# LED_Ring_Dimmer.net
KiCad netlist of a schematic drawn in EAGLE
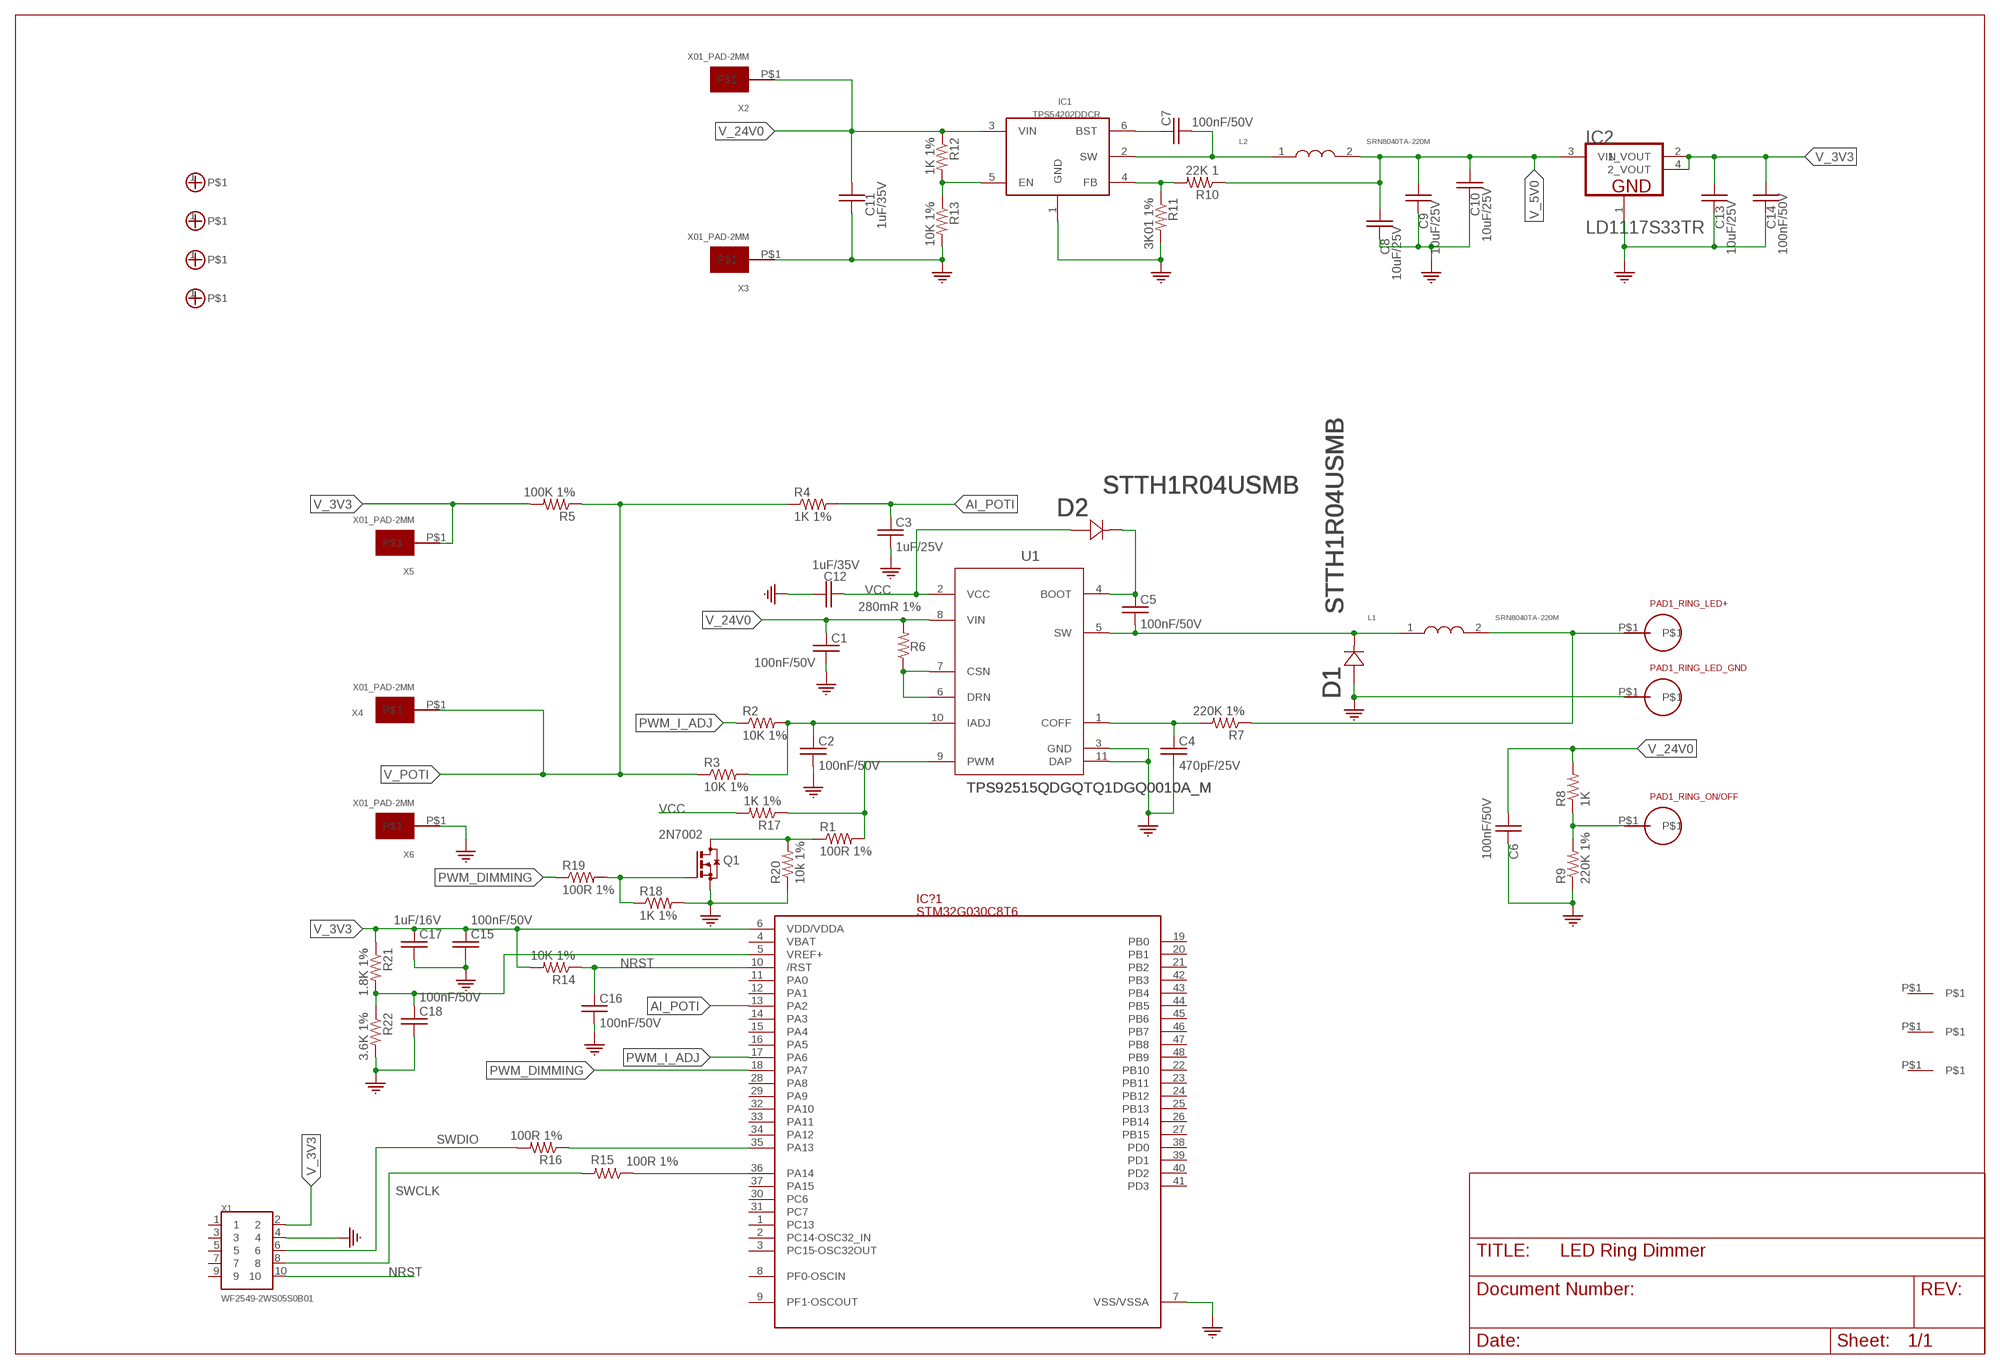
[diagram p0: schematic, sheet 1]

(export (version "E")
  (design (tool "Eeschema 10.0.6"))
  (components
    (comp (ref "C1")
      (value "100nF/50V")
      (footprint "eagle-import:EIA0603")
      (libsource (lib "eagle-import") (part "C_0603EIA0603"))
    )
    (comp (ref "C2")
      (value "100nF/50V")
      (footprint "eagle-import:EIA0603")
      (libsource (lib "eagle-import") (part "C_0603EIA0603"))
    )
    (comp (ref "C3")
      (value "1uF/25V")
      (footprint "eagle-import:EIA0603")
      (libsource (lib "eagle-import") (part "C_0603EIA0603"))
    )
    (comp (ref "C4")
      (value "470pF/25V")
      (footprint "eagle-import:EIA0603")
      (libsource (lib "eagle-import") (part "C_0603EIA0603"))
    )
    (comp (ref "C5")
      (value "100nF/50V")
      (footprint "eagle-import:EIA0603")
      (libsource (lib "eagle-import") (part "C_0603EIA0603"))
    )
    (comp (ref "C6")
      (value "100nF/50V")
      (footprint "eagle-import:EIA0603")
      (libsource (lib "eagle-import") (part "C_0603EIA0603"))
    )
    (comp (ref "C7")
      (value "100nF/50V")
      (footprint "eagle-import:EIA0603")
      (libsource (lib "eagle-import") (part "C_0603EIA0603"))
    )
    (comp (ref "C8")
      (value "10uF/25V")
      (footprint "eagle-import:EIA0603")
      (libsource (lib "eagle-import") (part "C_0603EIA0603"))
    )
    (comp (ref "C9")
      (value "10uF/25V")
      (footprint "eagle-import:EIA0603")
      (libsource (lib "eagle-import") (part "C_0603EIA0603"))
    )
    (comp (ref "C10")
      (value "10uF/25V")
      (footprint "eagle-import:EIA0603")
      (libsource (lib "eagle-import") (part "C_0603EIA0603"))
    )
    (comp (ref "C11")
      (value "1uF/35V")
      (footprint "eagle-import:EIA0603")
      (libsource (lib "eagle-import") (part "C_0603EIA0603"))
    )
    (comp (ref "C12")
      (value "1uF/35V")
      (footprint "eagle-import:EIA0603")
      (libsource (lib "eagle-import") (part "C_0603EIA0603"))
    )
    (comp (ref "C13")
      (value "10uF/25V")
      (footprint "eagle-import:EIA0603")
      (libsource (lib "eagle-import") (part "C_0603EIA0603"))
    )
    (comp (ref "C14")
      (value "100nF/50V")
      (footprint "eagle-import:EIA0603")
      (libsource (lib "eagle-import") (part "C_0603EIA0603"))
    )
    (comp (ref "C15")
      (value "100nF/50V")
      (footprint "eagle-import:EIA0603")
      (libsource (lib "eagle-import") (part "C_0603EIA0603"))
    )
    (comp (ref "C16")
      (value "100nF/50V")
      (footprint "eagle-import:EIA0603")
      (libsource (lib "eagle-import") (part "C_0603EIA0603"))
    )
    (comp (ref "C17")
      (value "1uF/16V")
      (footprint "eagle-import:EIA0603")
      (libsource (lib "eagle-import") (part "C_0603EIA0603"))
    )
    (comp (ref "C18")
      (value "100nF/50V")
      (footprint "eagle-import:EIA0603")
      (libsource (lib "eagle-import") (part "C_0603EIA0603"))
    )
    (comp (ref "D1")
      (value "STTH1R04USMB")
      (footprint "eagle-import:SMB")
      (libsource (lib "eagle-import") (part "STTH1R04USMB"))
    )
    (comp (ref "D2")
      (value "STTH1R04USMB")
      (footprint "eagle-import:SMB")
      (libsource (lib "eagle-import") (part "STTH1R04USMB"))
    )
    (comp (ref "FID1")
      (value "FIDUCIAL")
      (footprint "eagle-import:FIDUCIAL")
      (libsource (lib "eagle-import") (part "FIDUCIAL"))
    )
    (comp (ref "FID2")
      (value "FIDUCIAL")
      (footprint "eagle-import:FIDUCIAL")
      (libsource (lib "eagle-import") (part "FIDUCIAL"))
    )
    (comp (ref "FID3")
      (value "FIDUCIAL")
      (footprint "eagle-import:FIDUCIAL")
      (libsource (lib "eagle-import") (part "FIDUCIAL"))
    )
    (comp (ref "IC1")
      (value "TPS54202DDCR")
      (footprint "eagle-import:SOT23-6")
      (fields (field (name "MFR") "Texas Instruments"))
      (libsource (lib "eagle-import") (part "TPS54202DDCR"))
    )
    (comp (ref "IC2")
      (value "LD1117S33TR")
      (footprint "eagle-import:SOT223_LD1117S33TR")
      (fields (field (name "MFR") "STmicro, Diodes, TI,"))
      (libsource (lib "eagle-import") (part "LD1117S33TR"))
    )
    (comp (ref "IC?1")
      (value "STM32G030C8T6")
      (footprint "eagle-import:LQFP48")
      (libsource (lib "eagle-import") (part "STM32G030C8T6"))
    )
    (comp (ref "L1")
      (value "SRN8040TA-220M")
      (footprint "eagle-import:SRN8040TA-220M")
      (fields (field (name "MFR") "Bourns"))
      (libsource (lib "eagle-import") (part "SRN8040TA-220M"))
    )
    (comp (ref "L2")
      (value "SRN8040TA-220M")
      (footprint "eagle-import:SRN8040TA-220M")
      (fields (field (name "MFR") "Bourns"))
      (libsource (lib "eagle-import") (part "SRN8040TA-220M"))
    )
    (comp (ref "M1")
      (value "M_HOLE_3M")
      (footprint "eagle-import:PCB_SCREW_M3_POWER")
      (libsource (lib "eagle-import") (part "M_HOLE_3M"))
    )
    (comp (ref "M2")
      (value "M_HOLE_3M")
      (footprint "eagle-import:PCB_SCREW_M3_POWER")
      (libsource (lib "eagle-import") (part "M_HOLE_3M"))
    )
    (comp (ref "M3")
      (value "M_HOLE_3M")
      (footprint "eagle-import:PCB_SCREW_M3_POWER")
      (libsource (lib "eagle-import") (part "M_HOLE_3M"))
    )
    (comp (ref "M4")
      (value "M_HOLE_3M")
      (footprint "eagle-import:PCB_SCREW_M3_POWER")
      (libsource (lib "eagle-import") (part "M_HOLE_3M"))
    )
    (comp (ref "PAD1_RING_LED+")
      (value "THT_PAD_5MM")
      (footprint "eagle-import:THT_PAD_D5.0")
      (libsource (lib "eagle-import") (part "THT_PAD_5MM"))
    )
    (comp (ref "PAD1_RING_LED_GND")
      (value "THT_PAD_5MM")
      (footprint "eagle-import:THT_PAD_D5.0")
      (libsource (lib "eagle-import") (part "THT_PAD_5MM"))
    )
    (comp (ref "PAD1_RING_ON/OFF")
      (value "THT_PAD_5MM")
      (footprint "eagle-import:THT_PAD_D5.0")
      (libsource (lib "eagle-import") (part "THT_PAD_5MM"))
    )
    (comp (ref "Q1")
      (value "2N7002")
      (footprint "eagle-import:SOT23")
      (fields (field (name "MFR") "Diodes, Guangdong Hotetech,NXP"))
      (libsource (lib "eagle-import") (part "2N7002"))
    )
    (comp (ref "R1")
      (value "100R 1%")
      (footprint "eagle-import:EIA0603")
      (libsource (lib "eagle-import") (part "R_0603"))
    )
    (comp (ref "R2")
      (value "10K 1%")
      (footprint "eagle-import:EIA0603")
      (libsource (lib "eagle-import") (part "R_0603"))
    )
    (comp (ref "R3")
      (value "10K 1%")
      (footprint "eagle-import:EIA0603")
      (libsource (lib "eagle-import") (part "R_0603"))
    )
    (comp (ref "R4")
      (value "1K 1%")
      (footprint "eagle-import:EIA0603")
      (libsource (lib "eagle-import") (part "R_0603"))
    )
    (comp (ref "R5")
      (value "100K 1%")
      (footprint "eagle-import:EIA0603")
      (libsource (lib "eagle-import") (part "R_0603"))
    )
    (comp (ref "R6")
      (value "280mR 1%")
      (footprint "eagle-import:EIA1206")
      (libsource (lib "eagle-import") (part "R_1206EIA1206"))
    )
    (comp (ref "R7")
      (value "220K 1%")
      (footprint "eagle-import:EIA0603")
      (libsource (lib "eagle-import") (part "R_0603"))
    )
    (comp (ref "R8")
      (value "1K")
      (footprint "eagle-import:EIA0603")
      (libsource (lib "eagle-import") (part "R_0603"))
    )
    (comp (ref "R9")
      (value "220K 1%")
      (footprint "eagle-import:EIA0603")
      (libsource (lib "eagle-import") (part "R_0603"))
    )
    (comp (ref "R10")
      (value "22K 1")
      (footprint "eagle-import:EIA0603")
      (libsource (lib "eagle-import") (part "R_0603"))
    )
    (comp (ref "R11")
      (value "3K01 1%")
      (footprint "eagle-import:EIA0603")
      (libsource (lib "eagle-import") (part "R_0603"))
    )
    (comp (ref "R12")
      (value "1K 1%")
      (footprint "eagle-import:EIA0603")
      (libsource (lib "eagle-import") (part "R_0603"))
    )
    (comp (ref "R13")
      (value "10K 1%")
      (footprint "eagle-import:EIA0603")
      (libsource (lib "eagle-import") (part "R_0603"))
    )
    (comp (ref "R14")
      (value "10K 1%")
      (footprint "eagle-import:EIA0603")
      (libsource (lib "eagle-import") (part "R_0603"))
    )
    (comp (ref "R15")
      (value "100R 1%")
      (footprint "eagle-import:EIA0603")
      (libsource (lib "eagle-import") (part "R_0603"))
    )
    (comp (ref "R16")
      (value "100R 1%")
      (footprint "eagle-import:EIA0603")
      (libsource (lib "eagle-import") (part "R_0603"))
    )
    (comp (ref "R17")
      (value "1K 1%")
      (footprint "eagle-import:EIA0603")
      (libsource (lib "eagle-import") (part "R_0603"))
    )
    (comp (ref "R18")
      (value "1K 1%")
      (footprint "eagle-import:EIA0603")
      (libsource (lib "eagle-import") (part "R_0603"))
    )
    (comp (ref "R19")
      (value "100R 1%")
      (footprint "eagle-import:EIA0603")
      (libsource (lib "eagle-import") (part "R_0603"))
    )
    (comp (ref "R20")
      (value "10k 1%")
      (footprint "eagle-import:EIA0603")
      (libsource (lib "eagle-import") (part "R_0603"))
    )
    (comp (ref "R21")
      (value "1.8K 1%")
      (footprint "eagle-import:EIA0603")
      (libsource (lib "eagle-import") (part "R_0603"))
    )
    (comp (ref "R22")
      (value "3.6K 1%")
      (footprint "eagle-import:EIA0603")
      (libsource (lib "eagle-import") (part "R_0603"))
    )
    (comp (ref "U1")
      (value "TPS92515QDGQTQ1DGQ0010A_M")
      (footprint "eagle-import:DGQ0010A_M")
      (fields
        (field (name "MFR") "Texas Instruments")
        (field (name "COPYRIGHT") "Copyright (C) 2023 Ultra Librarian. All rights reserved.")
      )
      (libsource (lib "eagle-import") (part "TPS92515QDGQTQ1DGQ0010A_M"))
    )
    (comp (ref "X1")
      (value "WF2549-2WS05S0B01")
      (footprint "eagle-import:X10_100MIL_2XROW_VERT")
      (fields (field (name "MFR") "WCON"))
      (libsource (lib "eagle-import") (part "WF2549-2WS05S0B01"))
    )
    (comp (ref "X2")
      (value "X01_PAD-2MM")
      (footprint "eagle-import:X01_PAD-2MM")
      (libsource (lib "eagle-import") (part "X01_PAD-2MM"))
    )
    (comp (ref "X3")
      (value "X01_PAD-2MM")
      (footprint "eagle-import:X01_PAD-2MM")
      (libsource (lib "eagle-import") (part "X01_PAD-2MM"))
    )
    (comp (ref "X4")
      (value "X01_PAD-2MM")
      (footprint "eagle-import:X01_PAD-2MM")
      (libsource (lib "eagle-import") (part "X01_PAD-2MM"))
    )
    (comp (ref "X5")
      (value "X01_PAD-2MM")
      (footprint "eagle-import:X01_PAD-2MM")
      (libsource (lib "eagle-import") (part "X01_PAD-2MM"))
    )
    (comp (ref "X6")
      (value "X01_PAD-2MM")
      (footprint "eagle-import:X01_PAD-2MM")
      (libsource (lib "eagle-import") (part "X01_PAD-2MM"))
    )
  )
  (nets
    (net (code "1") (name "/NRST") (class "Default")
      (node (ref "C16") (pin "1") (pinfunction "1_1") (pintype "passive"))
      (node (ref "IC?1") (pin "10") (pinfunction "/RST_10") (pintype "bidirectional"))
      (node (ref "R14") (pin "1") (pinfunction "1_1") (pintype "passive"))
      (node (ref "X1") (pin "10") (pinfunction "10_10") (pintype "bidirectional"))
    )
    (net (code "2") (name "/SWCLK") (class "Default")
      (node (ref "R15") (pin "2") (pinfunction "2_2") (pintype "passive"))
      (node (ref "X1") (pin "8") (pinfunction "8_8") (pintype "bidirectional"))
    )
    (net (code "3") (name "/SWDIO") (class "Default")
      (node (ref "R16") (pin "2") (pinfunction "2_2") (pintype "passive"))
      (node (ref "X1") (pin "6") (pinfunction "6_6") (pintype "bidirectional"))
    )
    (net (code "4") (name "/VCC") (class "Default")
      (node (ref "C12") (pin "2") (pinfunction "2_2") (pintype "passive"))
      (node (ref "D2") (pin "A") (pinfunction "A_A") (pintype "passive"))
      (node (ref "R17") (pin "2") (pinfunction "2_2") (pintype "passive"))
      (node (ref "U1") (pin "2") (pinfunction "VCC_2") (pintype "power_in"))
    )
    (net (code "5") (name "AI_POTI") (class "Default")
      (node (ref "C3") (pin "1") (pinfunction "1_1") (pintype "passive"))
      (node (ref "IC?1") (pin "13") (pinfunction "PA2_13") (pintype "bidirectional"))
      (node (ref "R4") (pin "2") (pinfunction "2_2") (pintype "passive"))
    )
    (net (code "6") (name "GND") (class "Default")
      (node (ref "C1") (pin "2") (pinfunction "2_2") (pintype "passive"))
      (node (ref "C10") (pin "2") (pinfunction "2_2") (pintype "passive"))
      (node (ref "C11") (pin "2") (pinfunction "2_2") (pintype "passive"))
      (node (ref "C12") (pin "1") (pinfunction "1_1") (pintype "passive"))
      (node (ref "C13") (pin "2") (pinfunction "2_2") (pintype "passive"))
      (node (ref "C14") (pin "2") (pinfunction "2_2") (pintype "passive"))
      (node (ref "C15") (pin "2") (pinfunction "2_2") (pintype "passive"))
      (node (ref "C16") (pin "2") (pinfunction "2_2") (pintype "passive"))
      (node (ref "C17") (pin "2") (pinfunction "2_2") (pintype "passive"))
      (node (ref "C18") (pin "2") (pinfunction "2_2") (pintype "passive"))
      (node (ref "C2") (pin "2") (pinfunction "2_2") (pintype "passive"))
      (node (ref "C3") (pin "2") (pinfunction "2_2") (pintype "passive"))
      (node (ref "C4") (pin "2") (pinfunction "2_2") (pintype "passive"))
      (node (ref "C6") (pin "2") (pinfunction "2_2") (pintype "passive"))
      (node (ref "C8") (pin "2") (pinfunction "2_2") (pintype "passive"))
      (node (ref "C9") (pin "2") (pinfunction "2_2") (pintype "passive"))
      (node (ref "D1") (pin "A") (pinfunction "A_A") (pintype "passive"))
      (node (ref "IC1") (pin "1") (pinfunction "GND_1") (pintype "bidirectional"))
      (node (ref "IC2") (pin "1") (pinfunction "GND_1") (pintype "power_in"))
      (node (ref "IC?1") (pin "7") (pinfunction "VSS/VSSA_7") (pintype "bidirectional"))
      (node (ref "PAD1_RING_LED_GND") (pin "P$1") (pinfunction "P$1_P$1") (pintype "bidirectional"))
      (node (ref "Q1") (pin "2") (pinfunction "S_2") (pintype "passive"))
      (node (ref "R11") (pin "2") (pinfunction "2_2") (pintype "passive"))
      (node (ref "R13") (pin "2") (pinfunction "2_2") (pintype "passive"))
      (node (ref "R18") (pin "2") (pinfunction "2_2") (pintype "passive"))
      (node (ref "R20") (pin "1") (pinfunction "1_1") (pintype "passive"))
      (node (ref "R22") (pin "2") (pinfunction "2_2") (pintype "passive"))
      (node (ref "R9") (pin "1") (pinfunction "1_1") (pintype "passive"))
      (node (ref "U1") (pin "11") (pinfunction "DAP_11") (pintype "power_in"))
      (node (ref "U1") (pin "3") (pinfunction "GND_3") (pintype "power_in"))
      (node (ref "X1") (pin "4") (pinfunction "4_4") (pintype "bidirectional"))
      (node (ref "X3") (pin "P$1") (pinfunction "P$1_P$1") (pintype "bidirectional"))
      (node (ref "X6") (pin "P$1") (pinfunction "P$1_P$1") (pintype "bidirectional"))
    )
    (net (code "7") (name "Net-(D1-C)") (class "Default")
      (node (ref "C5") (pin "2") (pinfunction "2_2") (pintype "passive"))
      (node (ref "D1") (pin "K") (pinfunction "C_K") (pintype "passive"))
      (node (ref "L1") (pin "1") (pinfunction "P$1_1") (pintype "bidirectional"))
      (node (ref "U1") (pin "5") (pinfunction "SW_5") (pintype "power_in"))
    )
    (net (code "8") (name "Net-(D2-C)") (class "Default")
      (node (ref "C5") (pin "1") (pinfunction "1_1") (pintype "passive"))
      (node (ref "D2") (pin "K") (pinfunction "C_K") (pintype "passive"))
      (node (ref "U1") (pin "4") (pinfunction "BOOT_4") (pintype "power_in"))
    )
    (net (code "9") (name "Net-(IC1-BST)") (class "Default")
      (node (ref "C7") (pin "1") (pinfunction "1_1") (pintype "passive"))
      (node (ref "IC1") (pin "6") (pinfunction "BST_6") (pintype "bidirectional"))
    )
    (net (code "10") (name "Net-(IC1-EN)") (class "Default")
      (node (ref "IC1") (pin "5") (pinfunction "EN_5") (pintype "bidirectional"))
      (node (ref "R12") (pin "2") (pinfunction "2_2") (pintype "passive"))
      (node (ref "R13") (pin "1") (pinfunction "1_1") (pintype "passive"))
    )
    (net (code "11") (name "Net-(IC1-FB)") (class "Default")
      (node (ref "IC1") (pin "4") (pinfunction "FB_4") (pintype "bidirectional"))
      (node (ref "R10") (pin "2") (pinfunction "2_2") (pintype "passive"))
      (node (ref "R11") (pin "1") (pinfunction "1_1") (pintype "passive"))
    )
    (net (code "12") (name "Net-(IC1-SW)") (class "Default")
      (node (ref "C7") (pin "2") (pinfunction "2_2") (pintype "passive"))
      (node (ref "IC1") (pin "2") (pinfunction "SW_2") (pintype "bidirectional"))
      (node (ref "L2") (pin "1") (pinfunction "P$1_1") (pintype "bidirectional"))
    )
    (net (code "13") (name "Net-(IC?1-PA13)") (class "Default")
      (node (ref "IC?1") (pin "35") (pinfunction "PA13_35") (pintype "bidirectional"))
      (node (ref "R16") (pin "1") (pinfunction "1_1") (pintype "passive"))
    )
    (net (code "14") (name "Net-(IC?1-PA14)") (class "Default")
      (node (ref "IC?1") (pin "36") (pinfunction "PA14_36") (pintype "bidirectional"))
      (node (ref "R15") (pin "1") (pinfunction "1_1") (pintype "passive"))
    )
    (net (code "15") (name "Net-(IC?1-VREF+)") (class "Default")
      (node (ref "C18") (pin "1") (pinfunction "1_1") (pintype "passive"))
      (node (ref "IC?1") (pin "5") (pinfunction "VREF+_5") (pintype "bidirectional"))
      (node (ref "R21") (pin "2") (pinfunction "2_2") (pintype "passive"))
      (node (ref "R22") (pin "1") (pinfunction "1_1") (pintype "passive"))
    )
    (net (code "16") (name "Net-(L1-P$2)") (class "Default")
      (node (ref "L1") (pin "2") (pinfunction "P$2_2") (pintype "bidirectional"))
      (node (ref "PAD1_RING_LED+") (pin "P$1") (pinfunction "P$1_P$1") (pintype "bidirectional"))
      (node (ref "R7") (pin "1") (pinfunction "1_1") (pintype "passive"))
    )
    (net (code "17") (name "Net-(PAD1_RING_ON/OFF-PadP$1)") (class "Default")
      (node (ref "PAD1_RING_ON/OFF") (pin "P$1") (pinfunction "P$1_P$1") (pintype "bidirectional"))
      (node (ref "R8") (pin "1") (pinfunction "1_1") (pintype "passive"))
      (node (ref "R9") (pin "2") (pinfunction "2_2") (pintype "passive"))
    )
    (net (code "18") (name "Net-(Q1-D)") (class "Default")
      (node (ref "Q1") (pin "3") (pinfunction "D_3") (pintype "passive"))
      (node (ref "R1") (pin "1") (pinfunction "1_1") (pintype "passive"))
      (node (ref "R20") (pin "2") (pinfunction "2_2") (pintype "passive"))
    )
    (net (code "19") (name "Net-(Q1-G)") (class "Default")
      (node (ref "Q1") (pin "1") (pinfunction "G_1") (pintype "passive"))
      (node (ref "R18") (pin "1") (pinfunction "1_1") (pintype "passive"))
      (node (ref "R19") (pin "2") (pinfunction "2_2") (pintype "passive"))
    )
    (net (code "20") (name "Net-(U1-COFF)") (class "Default")
      (node (ref "C4") (pin "1") (pinfunction "1_1") (pintype "passive"))
      (node (ref "R7") (pin "2") (pinfunction "2_2") (pintype "passive"))
      (node (ref "U1") (pin "1") (pinfunction "COFF_1") (pintype "passive"))
    )
    (net (code "21") (name "Net-(U1-CSN)") (class "Default")
      (node (ref "R6") (pin "1") (pinfunction "1_1") (pintype "passive"))
      (node (ref "U1") (pin "6") (pinfunction "DRN_6") (pintype "passive"))
      (node (ref "U1") (pin "7") (pinfunction "CSN_7") (pintype "input"))
    )
    (net (code "22") (name "Net-(U1-IADJ)") (class "Default")
      (node (ref "C2") (pin "1") (pinfunction "1_1") (pintype "passive"))
      (node (ref "R2") (pin "2") (pinfunction "2_2") (pintype "passive"))
      (node (ref "R3") (pin "2") (pinfunction "2_2") (pintype "passive"))
      (node (ref "U1") (pin "10") (pinfunction "IADJ_10") (pintype "input"))
    )
    (net (code "23") (name "Net-(U1-PWM)") (class "Default")
      (node (ref "R1") (pin "2") (pinfunction "2_2") (pintype "passive"))
      (node (ref "R17") (pin "1") (pinfunction "1_1") (pintype "passive"))
      (node (ref "U1") (pin "9") (pinfunction "PWM_9") (pintype "input"))
    )
    (net (code "24") (name "Net-(U1-VIN)") (class "Default")
      (node (ref "C1") (pin "1") (pinfunction "1_1") (pintype "passive"))
      (node (ref "R6") (pin "2") (pinfunction "2_2") (pintype "passive"))
      (node (ref "U1") (pin "8") (pinfunction "VIN_8") (pintype "power_in"))
    )
    (net (code "25") (name "PWM_DIMMING") (class "Default")
      (node (ref "IC?1") (pin "18") (pinfunction "PA7_18") (pintype "bidirectional"))
      (node (ref "R19") (pin "1") (pinfunction "1_1") (pintype "passive"))
    )
    (net (code "26") (name "PWM_I_ADJ") (class "Default")
      (node (ref "IC?1") (pin "17") (pinfunction "PA6_17") (pintype "bidirectional"))
      (node (ref "R2") (pin "1") (pinfunction "1_1") (pintype "passive"))
    )
    (net (code "27") (name "V_3V3") (class "Default")
      (node (ref "C13") (pin "1") (pinfunction "1_1") (pintype "passive"))
      (node (ref "C14") (pin "1") (pinfunction "1_1") (pintype "passive"))
      (node (ref "C15") (pin "1") (pinfunction "1_1") (pintype "passive"))
      (node (ref "C17") (pin "1") (pinfunction "1_1") (pintype "passive"))
      (node (ref "IC2") (pin "2") (pinfunction "1_VOUT_2") (pintype "power_in"))
      (node (ref "IC2") (pin "4") (pinfunction "2_VOUT_4") (pintype "power_in"))
      (node (ref "IC?1") (pin "6") (pinfunction "VDD/VDDA_6") (pintype "bidirectional"))
      (node (ref "R14") (pin "2") (pinfunction "2_2") (pintype "passive"))
      (node (ref "R21") (pin "1") (pinfunction "1_1") (pintype "passive"))
      (node (ref "R5") (pin "2") (pinfunction "2_2") (pintype "passive"))
      (node (ref "X1") (pin "2") (pinfunction "2_2") (pintype "bidirectional"))
      (node (ref "X5") (pin "P$1") (pinfunction "P$1_P$1") (pintype "bidirectional"))
    )
    (net (code "28") (name "V_5V0") (class "Default")
      (node (ref "C10") (pin "1") (pinfunction "1_1") (pintype "passive"))
      (node (ref "C8") (pin "1") (pinfunction "1_1") (pintype "passive"))
      (node (ref "C9") (pin "1") (pinfunction "1_1") (pintype "passive"))
      (node (ref "IC2") (pin "3") (pinfunction "VIN_3") (pintype "power_in"))
      (node (ref "L2") (pin "2") (pinfunction "P$2_2") (pintype "bidirectional"))
      (node (ref "R10") (pin "1") (pinfunction "1_1") (pintype "passive"))
    )
    (net (code "29") (name "V_24V0") (class "Default")
      (node (ref "C11") (pin "1") (pinfunction "1_1") (pintype "passive"))
      (node (ref "C6") (pin "1") (pinfunction "1_1") (pintype "passive"))
      (node (ref "IC1") (pin "3") (pinfunction "VIN_3") (pintype "bidirectional"))
      (node (ref "R12") (pin "1") (pinfunction "1_1") (pintype "passive"))
      (node (ref "R8") (pin "2") (pinfunction "2_2") (pintype "passive"))
      (node (ref "X2") (pin "P$1") (pinfunction "P$1_P$1") (pintype "bidirectional"))
    )
    (net (code "30") (name "V_POTI") (class "Default")
      (node (ref "R3") (pin "1") (pinfunction "1_1") (pintype "passive"))
      (node (ref "R4") (pin "1") (pinfunction "1_1") (pintype "passive"))
      (node (ref "R5") (pin "1") (pinfunction "1_1") (pintype "passive"))
      (node (ref "X4") (pin "P$1") (pinfunction "P$1_P$1") (pintype "bidirectional"))
    )
    (net (code "31") (name "unconnected-(FID1-PadP$1)") (class "Default")
      (node (ref "FID1") (pin "P$1") (pinfunction "P$1_P$1") (pintype "bidirectional"))
    )
    (net (code "32") (name "unconnected-(FID2-PadP$1)") (class "Default")
      (node (ref "FID2") (pin "P$1") (pinfunction "P$1_P$1") (pintype "bidirectional"))
    )
    (net (code "33") (name "unconnected-(FID3-PadP$1)") (class "Default")
      (node (ref "FID3") (pin "P$1") (pinfunction "P$1_P$1") (pintype "bidirectional"))
    )
    (net (code "34") (name "unconnected-(IC?1-PA0-Pad11)") (class "Default")
      (node (ref "IC?1") (pin "11") (pinfunction "PA0_11") (pintype "bidirectional"))
    )
    (net (code "35") (name "unconnected-(IC?1-PA1-Pad12)") (class "Default")
      (node (ref "IC?1") (pin "12") (pinfunction "PA1_12") (pintype "bidirectional"))
    )
    (net (code "36") (name "unconnected-(IC?1-PA3-Pad14)") (class "Default")
      (node (ref "IC?1") (pin "14") (pinfunction "PA3_14") (pintype "bidirectional"))
    )
    (net (code "37") (name "unconnected-(IC?1-PA4-Pad15)") (class "Default")
      (node (ref "IC?1") (pin "15") (pinfunction "PA4_15") (pintype "bidirectional"))
    )
    (net (code "38") (name "unconnected-(IC?1-PA5-Pad16)") (class "Default")
      (node (ref "IC?1") (pin "16") (pinfunction "PA5_16") (pintype "bidirectional"))
    )
    (net (code "39") (name "unconnected-(IC?1-PA8-Pad28)") (class "Default")
      (node (ref "IC?1") (pin "28") (pinfunction "PA8_28") (pintype "bidirectional"))
    )
    (net (code "40") (name "unconnected-(IC?1-PA9-Pad29)") (class "Default")
      (node (ref "IC?1") (pin "29") (pinfunction "PA9_29") (pintype "bidirectional"))
    )
    (net (code "41") (name "unconnected-(IC?1-PA10-Pad32)") (class "Default")
      (node (ref "IC?1") (pin "32") (pinfunction "PA10_32") (pintype "bidirectional"))
    )
    (net (code "42") (name "unconnected-(IC?1-PA11-Pad33)") (class "Default")
      (node (ref "IC?1") (pin "33") (pinfunction "PA11_33") (pintype "bidirectional"))
    )
    (net (code "43") (name "unconnected-(IC?1-PA12-Pad34)") (class "Default")
      (node (ref "IC?1") (pin "34") (pinfunction "PA12_34") (pintype "bidirectional"))
    )
    (net (code "44") (name "unconnected-(IC?1-PA15-Pad37)") (class "Default")
      (node (ref "IC?1") (pin "37") (pinfunction "PA15_37") (pintype "bidirectional"))
    )
    (net (code "45") (name "unconnected-(IC?1-PB0-Pad19)") (class "Default")
      (node (ref "IC?1") (pin "19") (pinfunction "PB0_19") (pintype "bidirectional"))
    )
    (net (code "46") (name "unconnected-(IC?1-PB1-Pad20)") (class "Default")
      (node (ref "IC?1") (pin "20") (pinfunction "PB1_20") (pintype "bidirectional"))
    )
    (net (code "47") (name "unconnected-(IC?1-PB2-Pad21)") (class "Default")
      (node (ref "IC?1") (pin "21") (pinfunction "PB2_21") (pintype "bidirectional"))
    )
    (net (code "48") (name "unconnected-(IC?1-PB3-Pad42)") (class "Default")
      (node (ref "IC?1") (pin "42") (pinfunction "PB3_42") (pintype "bidirectional"))
    )
    (net (code "49") (name "unconnected-(IC?1-PB4-Pad43)") (class "Default")
      (node (ref "IC?1") (pin "43") (pinfunction "PB4_43") (pintype "bidirectional"))
    )
    (net (code "50") (name "unconnected-(IC?1-PB5-Pad44)") (class "Default")
      (node (ref "IC?1") (pin "44") (pinfunction "PB5_44") (pintype "bidirectional"))
    )
    (net (code "51") (name "unconnected-(IC?1-PB6-Pad45)") (class "Default")
      (node (ref "IC?1") (pin "45") (pinfunction "PB6_45") (pintype "bidirectional"))
    )
    (net (code "52") (name "unconnected-(IC?1-PB7-Pad46)") (class "Default")
      (node (ref "IC?1") (pin "46") (pinfunction "PB7_46") (pintype "bidirectional"))
    )
    (net (code "53") (name "unconnected-(IC?1-PB8-Pad47)") (class "Default")
      (node (ref "IC?1") (pin "47") (pinfunction "PB8_47") (pintype "bidirectional"))
    )
    (net (code "54") (name "unconnected-(IC?1-PB9-Pad48)") (class "Default")
      (node (ref "IC?1") (pin "48") (pinfunction "PB9_48") (pintype "bidirectional"))
    )
    (net (code "55") (name "unconnected-(IC?1-PB10-Pad22)") (class "Default")
      (node (ref "IC?1") (pin "22") (pinfunction "PB10_22") (pintype "bidirectional"))
    )
    (net (code "56") (name "unconnected-(IC?1-PB11-Pad23)") (class "Default")
      (node (ref "IC?1") (pin "23") (pinfunction "PB11_23") (pintype "bidirectional"))
    )
    (net (code "57") (name "unconnected-(IC?1-PB12-Pad24)") (class "Default")
      (node (ref "IC?1") (pin "24") (pinfunction "PB12_24") (pintype "bidirectional"))
    )
    (net (code "58") (name "unconnected-(IC?1-PB13-Pad25)") (class "Default")
      (node (ref "IC?1") (pin "25") (pinfunction "PB13_25") (pintype "bidirectional"))
    )
    (net (code "59") (name "unconnected-(IC?1-PB14-Pad26)") (class "Default")
      (node (ref "IC?1") (pin "26") (pinfunction "PB14_26") (pintype "bidirectional"))
    )
    (net (code "60") (name "unconnected-(IC?1-PB15-Pad27)") (class "Default")
      (node (ref "IC?1") (pin "27") (pinfunction "PB15_27") (pintype "bidirectional"))
    )
    (net (code "61") (name "unconnected-(IC?1-PC6-Pad30)") (class "Default")
      (node (ref "IC?1") (pin "30") (pinfunction "PC6_30") (pintype "bidirectional"))
    )
    (net (code "62") (name "unconnected-(IC?1-PC7-Pad31)") (class "Default")
      (node (ref "IC?1") (pin "31") (pinfunction "PC7_31") (pintype "bidirectional"))
    )
    (net (code "63") (name "unconnected-(IC?1-PC13-Pad1)") (class "Default")
      (node (ref "IC?1") (pin "1") (pinfunction "PC13_1") (pintype "bidirectional"))
    )
    (net (code "64") (name "unconnected-(IC?1-PC14-OSC32_IN-Pad2)") (class "Default")
      (node (ref "IC?1") (pin "2") (pinfunction "PC14-OSC32_IN_2") (pintype "bidirectional"))
    )
    (net (code "65") (name "unconnected-(IC?1-PC15-OSC32OUT-Pad3)") (class "Default")
      (node (ref "IC?1") (pin "3") (pinfunction "PC15-OSC32OUT_3") (pintype "bidirectional"))
    )
    (net (code "66") (name "unconnected-(IC?1-PD0-Pad38)") (class "Default")
      (node (ref "IC?1") (pin "38") (pinfunction "PD0_38") (pintype "bidirectional"))
    )
    (net (code "67") (name "unconnected-(IC?1-PD1-Pad39)") (class "Default")
      (node (ref "IC?1") (pin "39") (pinfunction "PD1_39") (pintype "bidirectional"))
    )
    (net (code "68") (name "unconnected-(IC?1-PD2-Pad40)") (class "Default")
      (node (ref "IC?1") (pin "40") (pinfunction "PD2_40") (pintype "bidirectional"))
    )
    (net (code "69") (name "unconnected-(IC?1-PD3-Pad41)") (class "Default")
      (node (ref "IC?1") (pin "41") (pinfunction "PD3_41") (pintype "bidirectional"))
    )
    (net (code "70") (name "unconnected-(IC?1-PF0-OSCIN-Pad8)") (class "Default")
      (node (ref "IC?1") (pin "8") (pinfunction "PF0-OSCIN_8") (pintype "bidirectional"))
    )
    (net (code "71") (name "unconnected-(IC?1-PF1-OSCOUT-Pad9)") (class "Default")
      (node (ref "IC?1") (pin "9") (pinfunction "PF1-OSCOUT_9") (pintype "bidirectional"))
    )
    (net (code "72") (name "unconnected-(IC?1-VBAT-Pad4)") (class "Default")
      (node (ref "IC?1") (pin "4") (pinfunction "VBAT_4") (pintype "bidirectional"))
    )
    (net (code "73") (name "unconnected-(M1-P$1-Pad1)") (class "Default")
      (node (ref "M1") (pin "1") (pinfunction "P$1_1") (pintype "bidirectional"))
    )
    (net (code "74") (name "unconnected-(M2-P$1-Pad1)") (class "Default")
      (node (ref "M2") (pin "1") (pinfunction "P$1_1") (pintype "bidirectional"))
    )
    (net (code "75") (name "unconnected-(M3-P$1-Pad1)") (class "Default")
      (node (ref "M3") (pin "1") (pinfunction "P$1_1") (pintype "bidirectional"))
    )
    (net (code "76") (name "unconnected-(M4-P$1-Pad1)") (class "Default")
      (node (ref "M4") (pin "1") (pinfunction "P$1_1") (pintype "bidirectional"))
    )
    (net (code "77") (name "unconnected-(X1-Pad1)") (class "Default")
      (node (ref "X1") (pin "1") (pinfunction "1_1") (pintype "bidirectional"))
    )
    (net (code "78") (name "unconnected-(X1-Pad3)") (class "Default")
      (node (ref "X1") (pin "3") (pinfunction "3_3") (pintype "bidirectional"))
    )
    (net (code "79") (name "unconnected-(X1-Pad5)") (class "Default")
      (node (ref "X1") (pin "5") (pinfunction "5_5") (pintype "bidirectional"))
    )
    (net (code "80") (name "unconnected-(X1-Pad7)") (class "Default")
      (node (ref "X1") (pin "7") (pinfunction "7_7") (pintype "bidirectional"))
    )
    (net (code "81") (name "unconnected-(X1-Pad9)") (class "Default")
      (node (ref "X1") (pin "9") (pinfunction "9_9") (pintype "bidirectional"))
    )
  )
)
